# CAM_BRD.net
KiCad netlist of a schematic drawn in Altium Designer
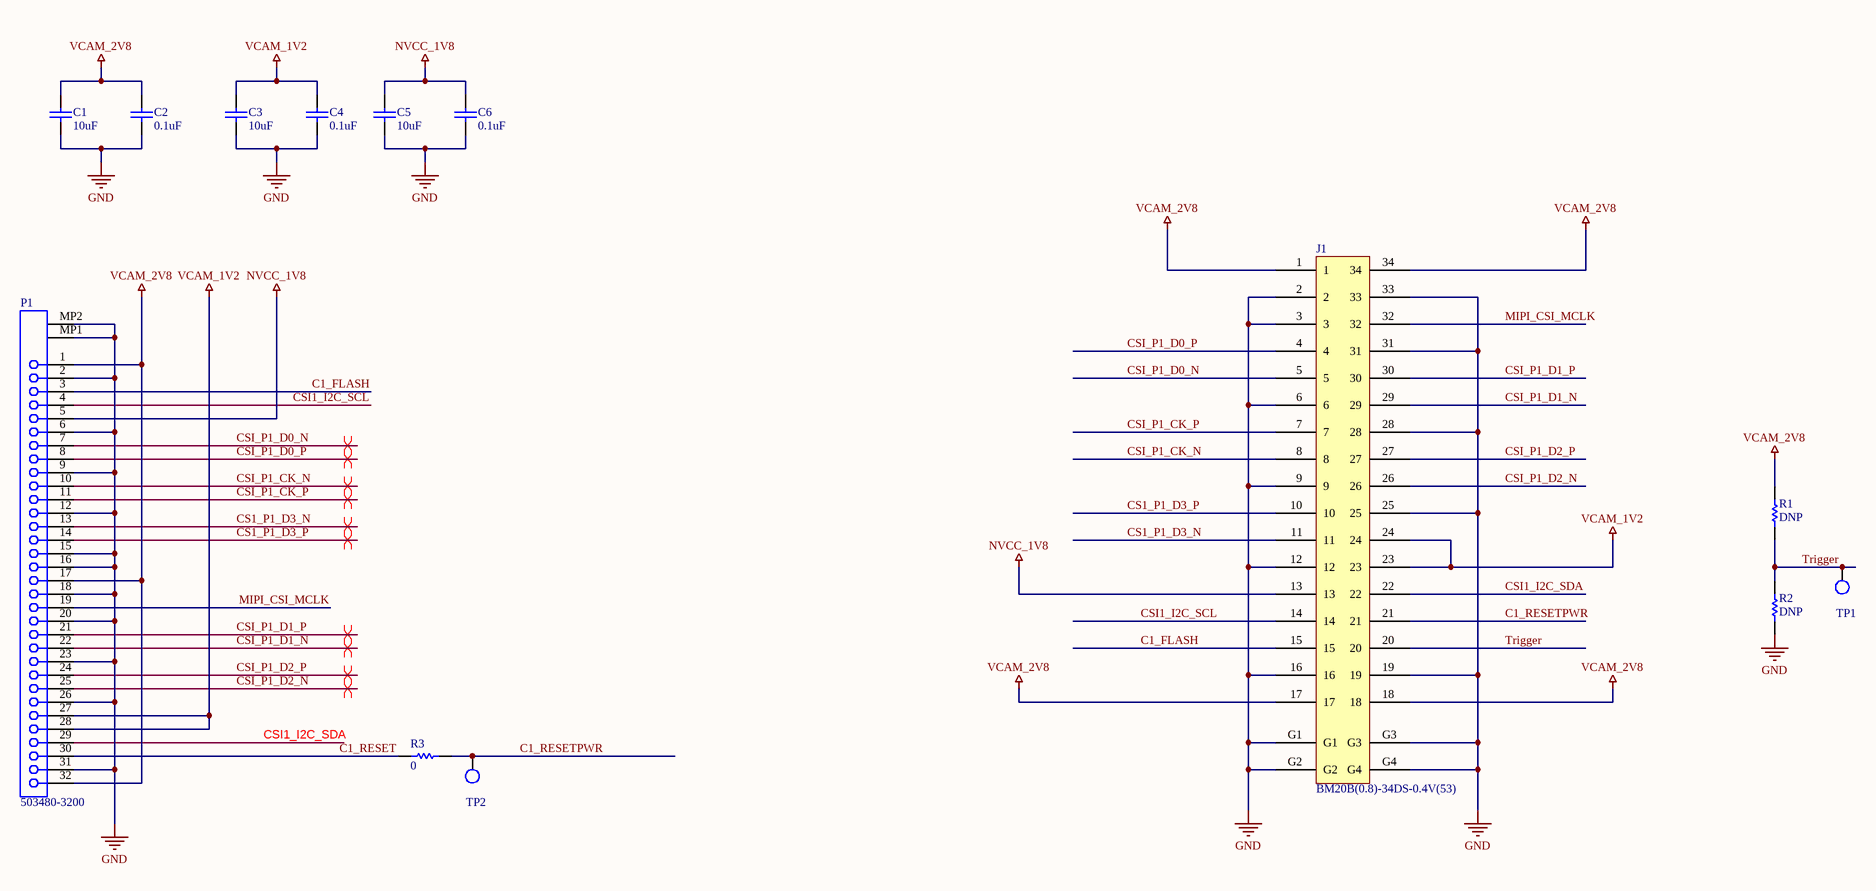
[diagram p0: CAM_BRD.SchDoc]

(export (version "E")
  (design (tool "Eeschema 10.0.6"))
  (components
    (comp (ref "C1")
      (value "10uF")
      (footprint "CAPC0402X06N")
      (description "CAP CER 10UF 10V X5R 0402")
      (libsource (lib "Passive") (part "Cap NP"))
    )
    (comp (ref "C2")
      (value "0.1uF")
      (footprint "CAPC0402X06N")
      (description "CAP CER 0.1UF 10V X7R 0402")
      (libsource (lib "Passive") (part "Cap NP"))
    )
    (comp (ref "C3")
      (value "10uF")
      (footprint "CAPC0402X06N")
      (description "CAP CER 10UF 10V X5R 0402")
      (libsource (lib "Passive") (part "Cap NP"))
    )
    (comp (ref "C4")
      (value "0.1uF")
      (footprint "CAPC0402X06N")
      (description "CAP CER 0.1UF 10V X7R 0402")
      (libsource (lib "Passive") (part "Cap NP"))
    )
    (comp (ref "C5")
      (value "10uF")
      (footprint "CAPC0402X06N")
      (description "CAP CER 10UF 10V X5R 0402")
      (libsource (lib "Passive") (part "Cap NP"))
    )
    (comp (ref "C6")
      (value "0.1uF")
      (footprint "CAPC0402X06N")
      (description "CAP CER 0.1UF 10V X7R 0402")
      (libsource (lib "Passive") (part "Cap NP"))
    )
    (comp (ref "J1")
      (value "BM20B(0.8)-34DS-0.4V(53)")
      (footprint "BM20")
      (description "34 Position Connector Receptacle, Center Strip Contacts Surface Mount Gold")
      (libsource (lib "CONN-BM20B(0.8)-34DS-0.4V(53)") (part "BM20B(0.8)-34DS-0.4V(53)"))
    )
    (comp (ref "P1")
      (value "503480-3200")
      (footprint "32POS-0.5MM PITCH")
      (libsource (lib "Connectors") (part "503480-3200"))
    )
    (comp (ref "R1")
      (value "DNP")
      (footprint "RESC0402X04N")
      (description "Resistor")
      (libsource (lib "Passive") (part "Res"))
    )
    (comp (ref "R2")
      (value "DNP")
      (footprint "RESC0402X04N")
      (description "Resistor")
      (libsource (lib "Passive") (part "Res"))
    )
    (comp (ref "R3")
      (value "0")
      (footprint "RESC0603X06N")
      (description "RES 0 OHM JUMPER 1/10W 0603")
      (libsource (lib "Passive") (part "Res"))
    )
    (comp (ref "TP1")
      (value "~")
      (footprint "Test Point")
      (description "Test point")
      (libsource (lib "Passive") (part "Test"))
    )
    (comp (ref "TP2")
      (value "~")
      (footprint "Test Point")
      (description "Test point")
      (libsource (lib "Passive") (part "Test"))
    )
  )
  (nets
    (net (code "1") (name "/C1_FLASH") (class "Default")
      (node (ref "J1") (pin "15") (pinfunction "15_15") (pintype "passive"))
      (node (ref "P1") (pin "3") (pinfunction "3_3") (pintype "passive"))
    )
    (net (code "2") (name "/C1_RESET") (class "Default")
      (node (ref "P1") (pin "30") (pinfunction "30_30") (pintype "passive"))
      (node (ref "R3") (pin "1") (pinfunction "1_1") (pintype "passive"))
    )
    (net (code "3") (name "/C1_RESETPWR") (class "Default")
      (node (ref "J1") (pin "21") (pinfunction "21_21") (pintype "passive"))
      (node (ref "R3") (pin "2") (pinfunction "2_2") (pintype "passive"))
      (node (ref "TP2") (pin "1") (pintype "passive"))
    )
    (net (code "4") (name "/CS1_P1_D3_N") (class "Default")
      (node (ref "J1") (pin "11") (pinfunction "11_11") (pintype "passive"))
      (node (ref "P1") (pin "13") (pinfunction "13_13") (pintype "passive"))
    )
    (net (code "5") (name "/CS1_P1_D3_P") (class "Default")
      (node (ref "J1") (pin "10") (pinfunction "10_10") (pintype "passive"))
      (node (ref "P1") (pin "14") (pinfunction "14_14") (pintype "passive"))
    )
    (net (code "6") (name "/CSI1_I2C_SCL") (class "Default")
      (node (ref "J1") (pin "14") (pinfunction "14_14") (pintype "passive"))
      (node (ref "P1") (pin "4") (pinfunction "4_4") (pintype "passive"))
    )
    (net (code "7") (name "/CSI1_I2C_SDA") (class "Default")
      (node (ref "J1") (pin "22") (pinfunction "22_22") (pintype "passive"))
      (node (ref "P1") (pin "29") (pinfunction "29_29") (pintype "passive"))
    )
    (net (code "8") (name "/CSI_P1_CK_N") (class "Default")
      (node (ref "J1") (pin "8") (pinfunction "8_8") (pintype "passive"))
      (node (ref "P1") (pin "10") (pinfunction "10_10") (pintype "passive"))
    )
    (net (code "9") (name "/CSI_P1_CK_P") (class "Default")
      (node (ref "J1") (pin "7") (pinfunction "7_7") (pintype "passive"))
      (node (ref "P1") (pin "11") (pinfunction "11_11") (pintype "passive"))
    )
    (net (code "10") (name "/CSI_P1_D0_N") (class "Default")
      (node (ref "J1") (pin "5") (pinfunction "5_5") (pintype "passive"))
      (node (ref "P1") (pin "7") (pinfunction "7_7") (pintype "passive"))
    )
    (net (code "11") (name "/CSI_P1_D0_P") (class "Default")
      (node (ref "J1") (pin "4") (pinfunction "4_4") (pintype "passive"))
      (node (ref "P1") (pin "8") (pinfunction "8_8") (pintype "passive"))
    )
    (net (code "12") (name "/CSI_P1_D1_N") (class "Default")
      (node (ref "J1") (pin "29") (pinfunction "29_29") (pintype "passive"))
      (node (ref "P1") (pin "22") (pinfunction "22_22") (pintype "passive"))
    )
    (net (code "13") (name "/CSI_P1_D1_P") (class "Default")
      (node (ref "J1") (pin "30") (pinfunction "30_30") (pintype "passive"))
      (node (ref "P1") (pin "21") (pinfunction "21_21") (pintype "passive"))
    )
    (net (code "14") (name "/CSI_P1_D2_N") (class "Default")
      (node (ref "J1") (pin "26") (pinfunction "26_26") (pintype "passive"))
      (node (ref "P1") (pin "25") (pinfunction "25_25") (pintype "passive"))
    )
    (net (code "15") (name "/CSI_P1_D2_P") (class "Default")
      (node (ref "J1") (pin "27") (pinfunction "27_27") (pintype "passive"))
      (node (ref "P1") (pin "24") (pinfunction "24_24") (pintype "passive"))
    )
    (net (code "16") (name "/MIPI_CSI_MCLK") (class "Default")
      (node (ref "J1") (pin "32") (pinfunction "32_32") (pintype "passive"))
      (node (ref "P1") (pin "19") (pinfunction "19_19") (pintype "passive"))
    )
    (net (code "17") (name "/Trigger") (class "Default")
      (node (ref "J1") (pin "20") (pinfunction "20_20") (pintype "passive"))
      (node (ref "R1") (pin "1") (pinfunction "1_1") (pintype "passive"))
      (node (ref "R2") (pin "2") (pinfunction "2_2") (pintype "passive"))
      (node (ref "TP1") (pin "1") (pintype "passive"))
    )
    (net (code "18") (name "GND") (class "Default")
      (node (ref "C1") (pin "1") (pinfunction "1_1") (pintype "passive"))
      (node (ref "C2") (pin "1") (pinfunction "1_1") (pintype "passive"))
      (node (ref "C3") (pin "1") (pinfunction "1_1") (pintype "passive"))
      (node (ref "C4") (pin "1") (pinfunction "1_1") (pintype "passive"))
      (node (ref "C5") (pin "1") (pinfunction "1_1") (pintype "passive"))
      (node (ref "C6") (pin "1") (pinfunction "1_1") (pintype "passive"))
      (node (ref "J1") (pin "12") (pinfunction "12_12") (pintype "passive"))
      (node (ref "J1") (pin "16") (pinfunction "16_16") (pintype "passive"))
      (node (ref "J1") (pin "19") (pinfunction "19_19") (pintype "passive"))
      (node (ref "J1") (pin "2") (pinfunction "2_2") (pintype "passive"))
      (node (ref "J1") (pin "25") (pinfunction "25_25") (pintype "passive"))
      (node (ref "J1") (pin "28") (pinfunction "28_28") (pintype "passive"))
      (node (ref "J1") (pin "3") (pinfunction "3_3") (pintype "passive"))
      (node (ref "J1") (pin "31") (pinfunction "31_31") (pintype "passive"))
      (node (ref "J1") (pin "33") (pinfunction "33_33") (pintype "passive"))
      (node (ref "J1") (pin "6") (pinfunction "6_6") (pintype "passive"))
      (node (ref "J1") (pin "9") (pinfunction "9_9") (pintype "passive"))
      (node (ref "J1") (pin "G1") (pinfunction "G1_G1") (pintype "passive"))
      (node (ref "J1") (pin "G2") (pinfunction "G2_G2") (pintype "passive"))
      (node (ref "J1") (pin "G3") (pinfunction "G3_G3") (pintype "passive"))
      (node (ref "J1") (pin "G4") (pinfunction "G4_G4") (pintype "passive"))
      (node (ref "P1") (pin "12") (pinfunction "12_12") (pintype "passive"))
      (node (ref "P1") (pin "15") (pinfunction "15_15") (pintype "passive"))
      (node (ref "P1") (pin "16") (pinfunction "16_16") (pintype "passive"))
      (node (ref "P1") (pin "18") (pinfunction "18_18") (pintype "passive"))
      (node (ref "P1") (pin "2") (pinfunction "2_2") (pintype "passive"))
      (node (ref "P1") (pin "20") (pinfunction "20_20") (pintype "passive"))
      (node (ref "P1") (pin "23") (pinfunction "23_23") (pintype "passive"))
      (node (ref "P1") (pin "26") (pinfunction "26_26") (pintype "passive"))
      (node (ref "P1") (pin "31") (pinfunction "31_31") (pintype "passive"))
      (node (ref "P1") (pin "6") (pinfunction "6_6") (pintype "passive"))
      (node (ref "P1") (pin "9") (pinfunction "9_9") (pintype "passive"))
      (node (ref "P1") (pin "MP1") (pinfunction "MP1_MP1") (pintype "passive"))
      (node (ref "P1") (pin "MP2") (pinfunction "MP2_MP2") (pintype "passive"))
      (node (ref "R2") (pin "1") (pinfunction "1_1") (pintype "passive"))
    )
    (net (code "19") (name "NVCC_1V8") (class "Default")
      (node (ref "C5") (pin "2") (pinfunction "2_2") (pintype "passive"))
      (node (ref "C6") (pin "2") (pinfunction "2_2") (pintype "passive"))
      (node (ref "J1") (pin "13") (pinfunction "13_13") (pintype "passive"))
      (node (ref "P1") (pin "5") (pinfunction "5_5") (pintype "passive"))
    )
    (net (code "20") (name "VCAM_1V2") (class "Default")
      (node (ref "C3") (pin "2") (pinfunction "2_2") (pintype "passive"))
      (node (ref "C4") (pin "2") (pinfunction "2_2") (pintype "passive"))
      (node (ref "J1") (pin "23") (pinfunction "23_23") (pintype "passive"))
      (node (ref "J1") (pin "24") (pinfunction "24_24") (pintype "passive"))
      (node (ref "P1") (pin "27") (pinfunction "27_27") (pintype "passive"))
      (node (ref "P1") (pin "28") (pinfunction "28_28") (pintype "passive"))
    )
    (net (code "21") (name "VCAM_2V8") (class "Default")
      (node (ref "C1") (pin "2") (pinfunction "2_2") (pintype "passive"))
      (node (ref "C2") (pin "2") (pinfunction "2_2") (pintype "passive"))
      (node (ref "J1") (pin "1") (pinfunction "1_1") (pintype "passive"))
      (node (ref "J1") (pin "17") (pinfunction "17_17") (pintype "passive"))
      (node (ref "J1") (pin "18") (pinfunction "18_18") (pintype "passive"))
      (node (ref "J1") (pin "34") (pinfunction "34_34") (pintype "passive"))
      (node (ref "P1") (pin "1") (pinfunction "1_1") (pintype "passive"))
      (node (ref "P1") (pin "17") (pinfunction "17_17") (pintype "passive"))
      (node (ref "P1") (pin "32") (pinfunction "32_32") (pintype "passive"))
      (node (ref "R1") (pin "2") (pinfunction "2_2") (pintype "passive"))
    )
  )
)
